# dual_CAN_conn.net
KiCad netlist of a schematic drawn in Altium Designer
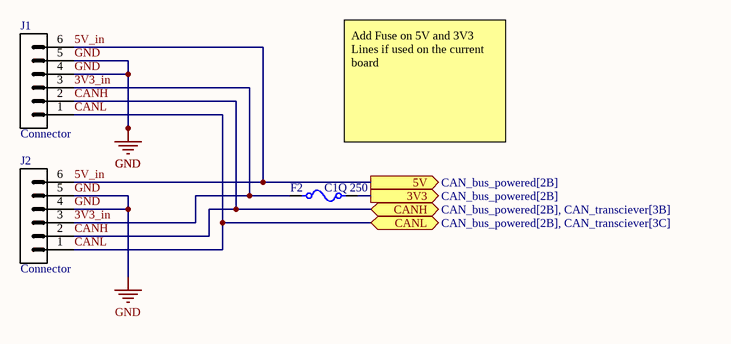
[diagram p0: dual_CAN_conn.SchDoc]

(export (version "E")
  (design (tool "Eeschema 10.0.6"))
  (components
    (comp (ref "F2")
      (value "C1Q 250")
      (footprint "Chip2PinSM127P600-8N")
      (description "Fuse")
      (libsource (lib "drfc_schlib") (part "Fuse"))
    )
    (comp (ref "J1")
      (value "Connector")
      (footprint "HRS_DF58-6P-1.2V(21)")
      (description "6 Pin 1 Row Connector")
      (libsource (lib "drfc_schlib") (part "Connector 6-Pin 1 Row"))
    )
    (comp (ref "J2")
      (value "Connector")
      (footprint "HRS_DF58-6P-1.2V(21)")
      (description "6 Pin 1 Row Connector")
      (libsource (lib "drfc_schlib") (part "Connector 6-Pin 1 Row"))
    )
  )
  (nets
    (net (code "1") (name "/3V3") (class "Default")
      (node (ref "F2") (pin "2") (pinfunction "2_2") (pintype "passive"))
    )
    (net (code "2") (name "/3V3_in") (class "Default")
      (node (ref "F2") (pin "1") (pinfunction "1_1") (pintype "passive"))
      (node (ref "J1") (pin "3") (pinfunction "3_3") (pintype "passive"))
      (node (ref "J2") (pin "3") (pinfunction "3_3") (pintype "passive"))
    )
    (net (code "3") (name "/5V_in") (class "Default")
      (node (ref "J1") (pin "6") (pinfunction "6_6") (pintype "passive"))
      (node (ref "J2") (pin "6") (pinfunction "6_6") (pintype "passive"))
    )
    (net (code "4") (name "/CANH") (class "Default")
      (node (ref "J1") (pin "2") (pinfunction "2_2") (pintype "passive"))
      (node (ref "J2") (pin "2") (pinfunction "2_2") (pintype "passive"))
    )
    (net (code "5") (name "/CANL") (class "Default")
      (node (ref "J1") (pin "1") (pinfunction "1_1") (pintype "passive"))
      (node (ref "J2") (pin "1") (pinfunction "1_1") (pintype "passive"))
    )
    (net (code "6") (name "GND") (class "Default")
      (node (ref "J1") (pin "4") (pinfunction "4_4") (pintype "passive"))
      (node (ref "J1") (pin "5") (pinfunction "5_5") (pintype "passive"))
      (node (ref "J2") (pin "4") (pinfunction "4_4") (pintype "passive"))
      (node (ref "J2") (pin "5") (pinfunction "5_5") (pintype "passive"))
    )
  )
)
